# EEPROM.net
KiCad netlist of a schematic drawn in Altium Designer
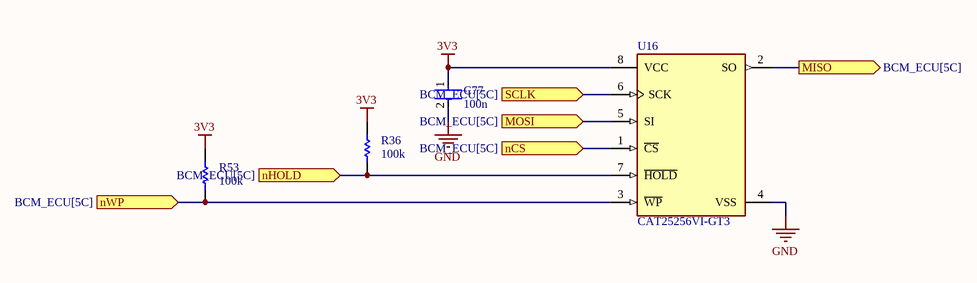
[diagram p0: EEPROM.SchDoc]

(export (version "E")
  (design (tool "Eeschema 10.0.6"))
  (components
    (comp (ref "C77")
      (value "100n")
      (footprint "FP-0402-L_1_0_0_05-W_0_5-IPC_A")
      (description "LARGE PADS, 0402 CAP, CHANGE COMMENT TO MATCH REAL P/N")
      (libsource (lib "Space Concordia") (part "b4654b650e69147ec39a6b967a45e02"))
    )
    (comp (ref "R36")
      (value "100k")
      (footprint "R0603B")
      (description "Resistor")
      (libsource (lib "Space Concordia") (part "Resistor"))
    )
    (comp (ref "R53")
      (value "100k")
      (footprint "R0603B")
      (description "Resistor")
      (libsource (lib "Space Concordia") (part "Resistor"))
    )
    (comp (ref "U16")
      (value "CAT25256VI-GT3")
      (footprint "FP-CAT25256VI-GT3-IPC_C")
      (description "IC EEPROM 256K SPI 20MHZ 8SOIC")
      (fields
        (field (name "MANUFACTURER") "ON Semiconductor")
        (field (name "OCTOPART") "https://octopart.com/cat25256vi-gt3-on+semiconductor-10567745")
      )
      (libsource (lib "Altium Content Vault") (part "19728d5809e14b24701e380846aa6e0"))
    )
  )
  (nets
    (net (code "1") (name "/MISO") (class "Default")
      (node (ref "U16") (pin "2") (pinfunction "SO_2") (pintype "output"))
    )
    (net (code "2") (name "/MOSI") (class "Default")
      (node (ref "U16") (pin "5") (pinfunction "SI_5") (pintype "input"))
    )
    (net (code "3") (name "/SCLK") (class "Default")
      (node (ref "U16") (pin "6") (pinfunction "SCK_6") (pintype "input"))
    )
    (net (code "4") (name "/nCS") (class "Default")
      (node (ref "U16") (pin "1") (pinfunction "~{CS}_1") (pintype "input"))
    )
    (net (code "5") (name "/nHOLD") (class "Default")
      (node (ref "R36") (pin "1") (pinfunction "1_1") (pintype "passive"))
      (node (ref "U16") (pin "7") (pinfunction "~{HOLD}_7") (pintype "input"))
    )
    (net (code "6") (name "/nWP") (class "Default")
      (node (ref "R53") (pin "1") (pinfunction "1_1") (pintype "passive"))
      (node (ref "U16") (pin "3") (pinfunction "~{WP}_3") (pintype "input"))
    )
    (net (code "7") (name "3V3") (class "Default")
      (node (ref "C77") (pin "1") (pinfunction "1_1") (pintype "passive"))
      (node (ref "R36") (pin "2") (pinfunction "2_2") (pintype "passive"))
      (node (ref "R53") (pin "2") (pinfunction "2_2") (pintype "passive"))
      (node (ref "U16") (pin "8") (pinfunction "VCC_8") (pintype "power_in"))
    )
    (net (code "8") (name "GND") (class "Default")
      (node (ref "C77") (pin "2") (pinfunction "2_2") (pintype "passive"))
      (node (ref "U16") (pin "4") (pinfunction "VSS_4") (pintype "power_in"))
    )
  )
)
